# power_supply.net
KiCad netlist of a schematic drawn in Altium Designer
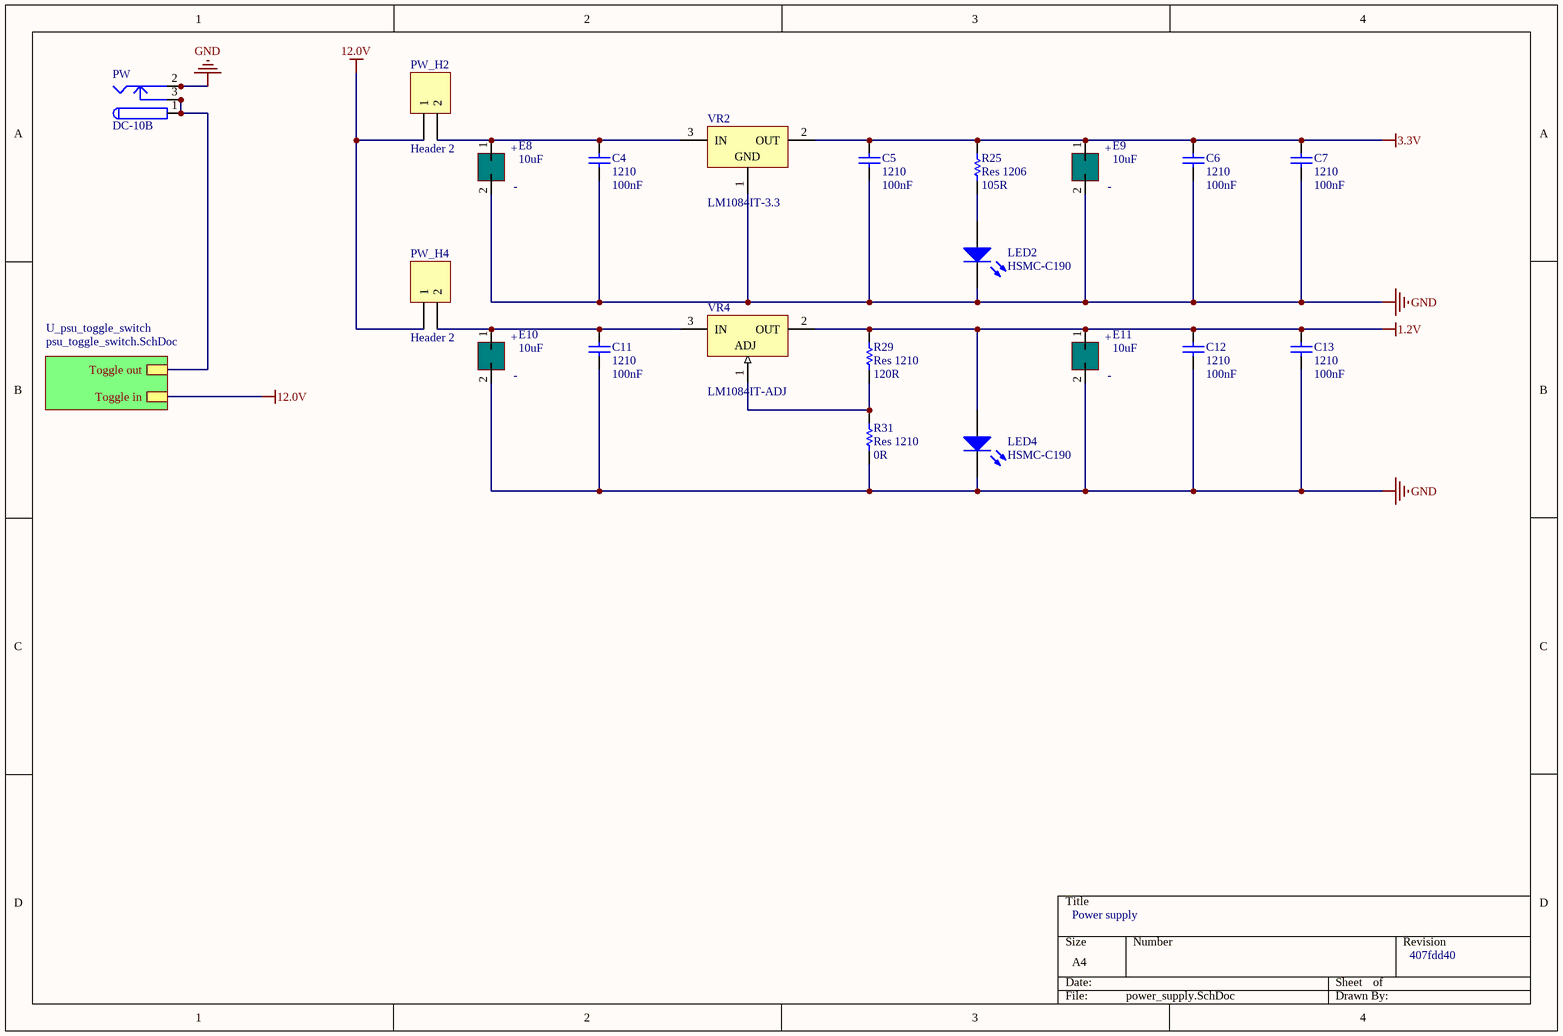
[diagram p0: power_supply.SchDoc]

(export (version "E")
  (design (tool "Eeschema 10.0.6"))
  (components
    (comp (ref "C4")
      (value "1210")
      (footprint "CAPC1210(3225)105_L")
      (description "CAP 100nF 100V ±5% 1210 (3225 Metric) Thickness 1.05mm SMD")
      (fields (field (name "TOLERANCE") "±5%") (field (name "ALTIUM_VALUE") "100nF"))
      (libsource (lib "Altium Content Vault") (part "CMP-1038-01663-1"))
    )
    (comp (ref "C5")
      (value "1210")
      (footprint "CAPC1210(3225)105_L")
      (description "CAP 100nF 100V ±5% 1210 (3225 Metric) Thickness 1.05mm SMD")
      (fields (field (name "TOLERANCE") "±5%") (field (name "ALTIUM_VALUE") "100nF"))
      (libsource (lib "Altium Content Vault") (part "CMP-1038-01663-1"))
    )
    (comp (ref "C6")
      (value "1210")
      (footprint "CAPC1210(3225)105_L")
      (description "CAP 100nF 100V ±5% 1210 (3225 Metric) Thickness 1.05mm SMD")
      (fields (field (name "TOLERANCE") "±5%") (field (name "ALTIUM_VALUE") "100nF"))
      (libsource (lib "Altium Content Vault") (part "CMP-1038-01663-1"))
    )
    (comp (ref "C7")
      (value "1210")
      (footprint "CAPC1210(3225)105_L")
      (description "CAP 100nF 100V ±5% 1210 (3225 Metric) Thickness 1.05mm SMD")
      (fields (field (name "TOLERANCE") "±5%") (field (name "ALTIUM_VALUE") "100nF"))
      (libsource (lib "Altium Content Vault") (part "CMP-1038-01663-1"))
    )
    (comp (ref "C11")
      (value "1210")
      (footprint "CAPC1210(3225)105_L")
      (description "CAP 100nF 100V ±5% 1210 (3225 Metric) Thickness 1.05mm SMD")
      (fields (field (name "TOLERANCE") "±5%") (field (name "ALTIUM_VALUE") "100nF"))
      (libsource (lib "Altium Content Vault") (part "CMP-1038-01663-1"))
    )
    (comp (ref "C12")
      (value "1210")
      (footprint "CAPC1210(3225)105_L")
      (description "CAP 100nF 100V ±5% 1210 (3225 Metric) Thickness 1.05mm SMD")
      (fields (field (name "TOLERANCE") "±5%") (field (name "ALTIUM_VALUE") "100nF"))
      (libsource (lib "Altium Content Vault") (part "CMP-1038-01663-1"))
    )
    (comp (ref "C13")
      (value "1210")
      (footprint "CAPC1210(3225)105_L")
      (description "CAP 100nF 100V ±5% 1210 (3225 Metric) Thickness 1.05mm SMD")
      (fields (field (name "TOLERANCE") "±5%") (field (name "ALTIUM_VALUE") "100nF"))
      (libsource (lib "Altium Content Vault") (part "CMP-1038-01663-1"))
    )
    (comp (ref "E8")
      (value "10uF")
      (footprint "cap_pol_size_B")
      (description "size B series S type V capacitor, panasonic elec")
      (libsource (lib "cap-pol-size-B") (part "CAP_POL_SIZE_B"))
    )
    (comp (ref "E9")
      (value "10uF")
      (footprint "cap_pol_size_B")
      (description "size B series S type V capacitor, panasonic elec")
      (libsource (lib "cap-pol-size-B") (part "CAP_POL_SIZE_B"))
    )
    (comp (ref "E10")
      (value "10uF")
      (footprint "cap_pol_size_B")
      (description "size B series S type V capacitor, panasonic elec")
      (libsource (lib "cap-pol-size-B") (part "CAP_POL_SIZE_B"))
    )
    (comp (ref "E11")
      (value "10uF")
      (footprint "cap_pol_size_B")
      (description "size B series S type V capacitor, panasonic elec")
      (libsource (lib "cap-pol-size-B") (part "CAP_POL_SIZE_B"))
    )
    (comp (ref "LED2")
      (value "HSMC-C190")
      (footprint "1.6X0.8X0.8")
      (description "High Performance Chip LED, Red")
      (fields (field (name "PUBLISHER") "Altium Limited"))
      (libsource (lib "Avago Optoelectronic LED") (part "HSMC-C190"))
    )
    (comp (ref "LED4")
      (value "HSMC-C190")
      (footprint "1.6X0.8X0.8")
      (description "High Performance Chip LED, Red")
      (fields (field (name "PUBLISHER") "Altium Limited"))
      (libsource (lib "Avago Optoelectronic LED") (part "HSMC-C190"))
    )
    (comp (ref "PW")
      (value "DC-10B")
      (footprint "KLD-0202")
      (description "Low Voltage Power Supply Connector")
      (fields (field (name "PUBLISHER") "Altium Limited"))
      (libsource (lib "Miscellaneous Connectors") (part "PWR2.5"))
    )
    (comp (ref "PW_H2")
      (value "Header 2")
      (footprint "HDR1X2")
      (description "Header, 2-Pin")
      (fields (field (name "PUBLISHER") "Altium Limited"))
      (libsource (lib "Miscellaneous Connectors") (part "Header 2"))
    )
    (comp (ref "PW_H4")
      (value "Header 2")
      (footprint "HDR1X2")
      (description "Header, 2-Pin")
      (fields (field (name "PUBLISHER") "Altium Limited"))
      (libsource (lib "Miscellaneous Connectors") (part "Header 2"))
    )
    (comp (ref "R25")
      (value "Res 1206")
      (footprint "RESC1206(3216)_L")
      (description "105R 0.25W 5% 1206 (3216 Metric)  SMD")
      (fields
        (field (name "TOLERANCE") "5 %")
        (field (name "ALTIUM_VALUE") "105R")
        (field (name "POWER") "0.25 W")
      )
      (libsource (lib "Altium Content Vault") (part "CMP-1014-00056-1"))
    )
    (comp (ref "R29")
      (value "Res 1210")
      (footprint "RESC1210(3225)_M")
      (description "120R 0.5W 1% 1210 (3225 Metric)  SMD")
      (fields
        (field (name "TOLERANCE") "1 %")
        (field (name "POWER") "0.5 W")
        (field (name "ALTIUM_VALUE") "120R")
      )
      (libsource (lib "Altium Content Vault") (part "CMP-1015-00405-1"))
    )
    (comp (ref "R31")
      (value "Res 1210")
      (footprint "RESC1210(3225)_M")
      (description "0R 0.5W 1% 1210 (3225 Metric)  SMD")
      (fields
        (field (name "TOLERANCE") "1 %")
        (field (name "POWER") "0.5 W")
        (field (name "ALTIUM_VALUE") "0R")
      )
      (libsource (lib "Altium Content Vault") (part "CMP-1015-00405-1"))
    )
    (comp (ref "VR2")
      (value "LM1084IT-3.3")
      (footprint "T03B")
      (description "5A Low Dropout Positive Regulators, 3-pin TO-220")
      (fields
        (field (name "MANUFACTURER") "National Semiconductor")
        (field (name "PUBLISHER") "Altium Limited")
      )
      (libsource (lib "NSC LDO") (part "LM1084IT-3.3"))
    )
    (comp (ref "VR4")
      (value "LM1084IT-ADJ")
      (footprint "T03B")
      (description "5A Low Dropout Positive Regulators, 3-pin TO-220")
      (fields
        (field (name "MANUFACTURER") "National Semiconductor")
        (field (name "PUBLISHER") "Altium Limited")
      )
      (libsource (lib "NSC LDO") (part "LM1084IT-ADJ"))
    )
  )
  (nets
    (net (code "1") (name "/Toggle out") (class "Default")
      (node (ref "PW") (pin "1") (pinfunction "1_1") (pintype "power_in"))
      (node (ref "PW") (pin "1A") (pinfunction "1A_1A") (pintype "power_in"))
      (node (ref "PW") (pin "1B") (pinfunction "1B_1B") (pintype "power_in"))
      (node (ref "PW") (pin "3") (pinfunction "3_3") (pintype "power_in"))
      (node (ref "PW") (pin "3A") (pinfunction "3A_3A") (pintype "power_in"))
      (node (ref "PW") (pin "3B") (pinfunction "3B_3B") (pintype "power_in"))
    )
    (net (code "2") (name "1.2V") (class "Default")
      (node (ref "C12") (pin "2") (pinfunction "2_2") (pintype "passive"))
      (node (ref "C13") (pin "2") (pinfunction "2_2") (pintype "passive"))
      (node (ref "E11") (pin "1") (pinfunction "1_1") (pintype "passive"))
      (node (ref "LED4") (pin "1") (pinfunction "A_1") (pintype "passive"))
      (node (ref "R29") (pin "2") (pinfunction "2_2") (pintype "passive"))
      (node (ref "VR4") (pin "2") (pinfunction "OUT_2") (pintype "power_in"))
    )
    (net (code "3") (name "3.3V") (class "Default")
      (node (ref "C5") (pin "2") (pinfunction "2_2") (pintype "passive"))
      (node (ref "C6") (pin "2") (pinfunction "2_2") (pintype "passive"))
      (node (ref "C7") (pin "2") (pinfunction "2_2") (pintype "passive"))
      (node (ref "E9") (pin "1") (pinfunction "1_1") (pintype "passive"))
      (node (ref "R25") (pin "1") (pinfunction "1_1") (pintype "passive"))
      (node (ref "VR2") (pin "2") (pinfunction "OUT_2") (pintype "power_in"))
    )
    (net (code "4") (name "12.0V") (class "Default")
      (node (ref "PW_H2") (pin "1") (pinfunction "1_1") (pintype "passive"))
      (node (ref "PW_H4") (pin "1") (pinfunction "1_1") (pintype "passive"))
    )
    (net (code "5") (name "GND") (class "Default")
      (node (ref "C11") (pin "1") (pinfunction "1_1") (pintype "passive"))
      (node (ref "C12") (pin "1") (pinfunction "1_1") (pintype "passive"))
      (node (ref "C13") (pin "1") (pinfunction "1_1") (pintype "passive"))
      (node (ref "C4") (pin "1") (pinfunction "1_1") (pintype "passive"))
      (node (ref "C5") (pin "1") (pinfunction "1_1") (pintype "passive"))
      (node (ref "C6") (pin "1") (pinfunction "1_1") (pintype "passive"))
      (node (ref "C7") (pin "1") (pinfunction "1_1") (pintype "passive"))
      (node (ref "E10") (pin "2") (pinfunction "2_2") (pintype "passive"))
      (node (ref "E11") (pin "2") (pinfunction "2_2") (pintype "passive"))
      (node (ref "E8") (pin "2") (pinfunction "2_2") (pintype "passive"))
      (node (ref "E9") (pin "2") (pinfunction "2_2") (pintype "passive"))
      (node (ref "LED2") (pin "2") (pinfunction "K_2") (pintype "passive"))
      (node (ref "LED4") (pin "2") (pinfunction "K_2") (pintype "passive"))
      (node (ref "PW") (pin "2") (pinfunction "2_2") (pintype "power_in"))
      (node (ref "PW") (pin "2A") (pinfunction "2A_2A") (pintype "power_in"))
      (node (ref "PW") (pin "2B") (pinfunction "2B_2B") (pintype "power_in"))
      (node (ref "R31") (pin "1") (pinfunction "1_1") (pintype "passive"))
      (node (ref "VR2") (pin "1") (pinfunction "GND_1") (pintype "power_in"))
    )
    (net (code "6") (name "Net-(LED2-A)") (class "Default")
      (node (ref "LED2") (pin "1") (pinfunction "A_1") (pintype "passive"))
      (node (ref "R25") (pin "2") (pinfunction "2_2") (pintype "passive"))
    )
    (net (code "7") (name "Net-(VR2-IN)") (class "Default")
      (node (ref "C4") (pin "2") (pinfunction "2_2") (pintype "passive"))
      (node (ref "E8") (pin "1") (pinfunction "1_1") (pintype "passive"))
      (node (ref "PW_H2") (pin "2") (pinfunction "2_2") (pintype "passive"))
      (node (ref "VR2") (pin "3") (pinfunction "IN_3") (pintype "power_in"))
    )
    (net (code "8") (name "Net-(VR4-ADJ)") (class "Default")
      (node (ref "R29") (pin "1") (pinfunction "1_1") (pintype "passive"))
      (node (ref "R31") (pin "2") (pinfunction "2_2") (pintype "passive"))
      (node (ref "VR4") (pin "1") (pinfunction "ADJ_1") (pintype "input"))
    )
    (net (code "9") (name "Net-(VR4-IN)") (class "Default")
      (node (ref "C11") (pin "2") (pinfunction "2_2") (pintype "passive"))
      (node (ref "E10") (pin "1") (pinfunction "1_1") (pintype "passive"))
      (node (ref "PW_H4") (pin "2") (pinfunction "2_2") (pintype "passive"))
      (node (ref "VR4") (pin "3") (pinfunction "IN_3") (pintype "power_in"))
    )
  )
)
